# SAS_rev04.net
KiCad netlist of a schematic drawn in EAGLE
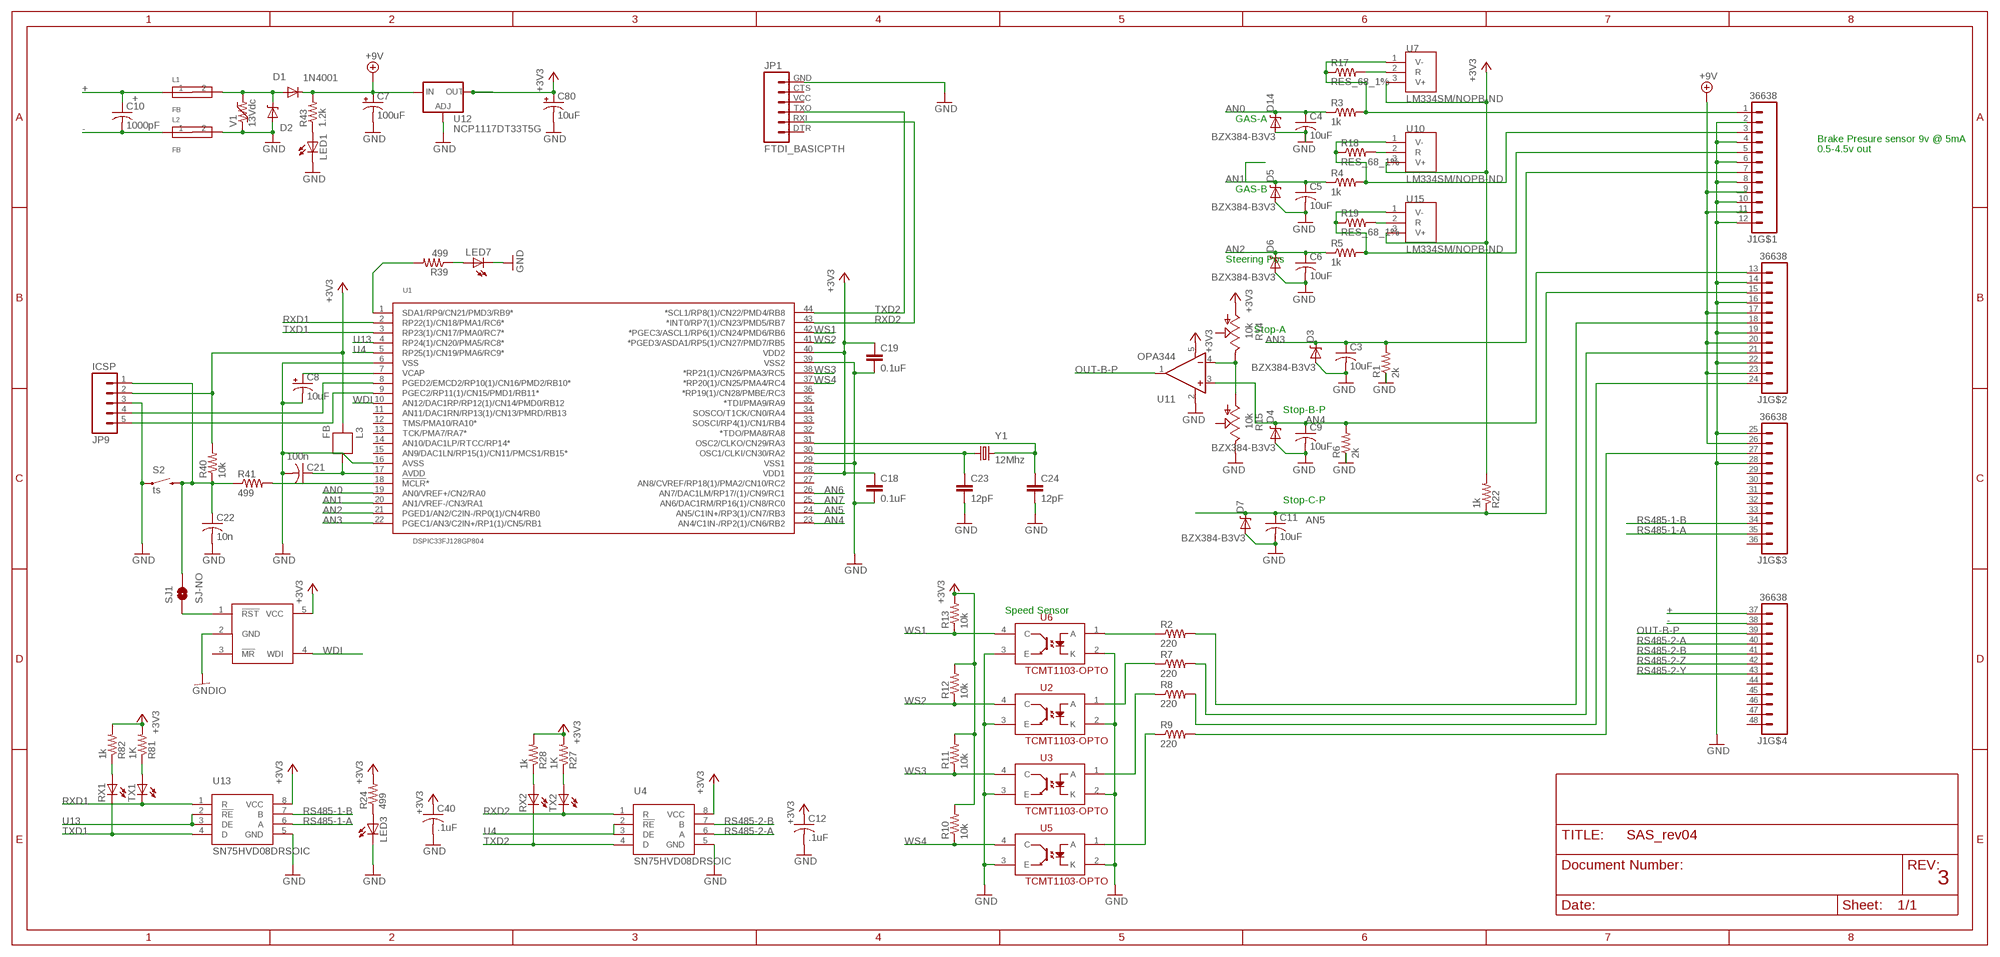
[diagram p0: schematic, sheet 1]

(export (version "E")
  (design (tool "Eeschema 10.0.6"))
  (components
    (comp (ref "C3")
      (value "10uF")
      (footprint "eagle-import:C0805")
      (libsource (lib "eagle-import") (part "C-USC0805"))
    )
    (comp (ref "C4")
      (value "10uF")
      (footprint "eagle-import:C0805")
      (libsource (lib "eagle-import") (part "C-USC0805"))
    )
    (comp (ref "C5")
      (value "10uF")
      (footprint "eagle-import:C0805")
      (libsource (lib "eagle-import") (part "C-USC0805"))
    )
    (comp (ref "C6")
      (value "10uF")
      (footprint "eagle-import:C0805")
      (libsource (lib "eagle-import") (part "C-USC0805"))
    )
    (comp (ref "C7")
      (value "100uF")
      (footprint "eagle-import:EIA7343")
      (libsource (lib "eagle-import") (part "CAP_POL7343"))
    )
    (comp (ref "C8")
      (value "10uF")
      (footprint "eagle-import:EIA3216-16V")
      (fields (field (name "PARTNO") "T491A106M016AT"))
      (libsource (lib "eagle-import") (part "CAP-POL_10UF_16V"))
    )
    (comp (ref "C9")
      (value "10uF")
      (footprint "eagle-import:C0805")
      (libsource (lib "eagle-import") (part "C-USC0805"))
    )
    (comp (ref "C10")
      (value "1000pF")
      (footprint "eagle-import:C1825")
      (libsource (lib "eagle-import") (part "C-USC1825"))
    )
    (comp (ref "C11")
      (value "10uF")
      (footprint "eagle-import:C0805")
      (libsource (lib "eagle-import") (part "C-USC0805"))
    )
    (comp (ref "C12")
      (value ".1uF")
      (footprint "eagle-import:0603")
      (fields (field (name "PARTNO") "CC0603ZRY5V9BB104"))
      (libsource (lib "eagle-import") (part "CAP_0.1UF_50V"))
    )
    (comp (ref "C18")
      (value "0.1uF")
      (footprint "eagle-import:0805")
      (libsource (lib "eagle-import") (part "CAP0805"))
    )
    (comp (ref "C19")
      (value "0.1uF")
      (footprint "eagle-import:0805")
      (libsource (lib "eagle-import") (part "CAP0805"))
    )
    (comp (ref "C21")
      (value "100n")
      (footprint "eagle-import:C0805")
      (libsource (lib "eagle-import") (part "C-USC0805"))
    )
    (comp (ref "C22")
      (value "10n")
      (footprint "eagle-import:0603")
      (fields (field (name "PARTNO") "CL10F103ZB8NNNC"))
      (libsource (lib "eagle-import") (part "CAP_10NF_50V"))
    )
    (comp (ref "C23")
      (value "12pF")
      (footprint "eagle-import:0805")
      (libsource (lib "eagle-import") (part "CAP0805"))
    )
    (comp (ref "C24")
      (value "12pF")
      (footprint "eagle-import:0805")
      (libsource (lib "eagle-import") (part "CAP0805"))
    )
    (comp (ref "C40")
      (value ".1uF")
      (footprint "eagle-import:0603")
      (fields (field (name "PARTNO") "CC0603ZRY5V9BB104"))
      (libsource (lib "eagle-import") (part "CAP_0.1UF_50V"))
    )
    (comp (ref "C80")
      (value "10uF")
      (footprint "eagle-import:POLC1206")
      (libsource (lib "eagle-import") (part "POLCAP"))
    )
    (comp (ref "D1")
      (value "1N4001")
      (footprint "eagle-import:SOD123")
      (libsource (lib "eagle-import") (part "DIODE-SOD123"))
    )
    (comp (ref "D2")
      (value "MM5Z30")
      (footprint "eagle-import:SOD-523F")
      (libsource (lib "eagle-import") (part "MM5Z30"))
    )
    (comp (ref "D3")
      (value "BZX384-B3V3")
      (footprint "eagle-import:SOD-323")
      (libsource (lib "eagle-import") (part "DIODE-ZENER-BZT52"))
    )
    (comp (ref "D4")
      (value "BZX384-B3V3")
      (footprint "eagle-import:SOD-323")
      (libsource (lib "eagle-import") (part "DIODE-ZENER-BZT52"))
    )
    (comp (ref "D5")
      (value "BZX384-B3V3")
      (footprint "eagle-import:SOD-323")
      (libsource (lib "eagle-import") (part "DIODE-ZENER-BZT52"))
    )
    (comp (ref "D6")
      (value "BZX384-B3V3")
      (footprint "eagle-import:SOD-323")
      (libsource (lib "eagle-import") (part "DIODE-ZENER-BZT52"))
    )
    (comp (ref "D7")
      (value "BZX384-B3V3")
      (footprint "eagle-import:SOD-323")
      (libsource (lib "eagle-import") (part "DIODE-ZENER-BZT52"))
    )
    (comp (ref "D14")
      (value "BZX384-B3V3")
      (footprint "eagle-import:SOD-323")
      (libsource (lib "eagle-import") (part "DIODE-ZENER-BZT52"))
    )
    (comp (ref "J1")
      (value "36638")
      (footprint "eagle-import:36638")
      (fields (field (name "PARTNO") "0366380002"))
      (libsource (lib "eagle-import") (part "36638"))
    )
    (comp (ref "JP1")
      (value "FTDI_BASICPTH")
      (footprint "eagle-import:FTDI_BASIC")
      (libsource (lib "eagle-import") (part "FTDI_BASICPTH"))
    )
    (comp (ref "JP9")
      (value "ICSP")
      (footprint "eagle-import:1X05_LOCK_LONGPADS")
      (libsource (lib "eagle-import") (part "M05LOCK_LONGPADS"))
    )
    (comp (ref "L1")
      (value "FB")
      (footprint "eagle-import:0603")
      (libsource (lib "eagle-import") (part "FERITEBEAD"))
    )
    (comp (ref "L2")
      (value "FB")
      (footprint "eagle-import:0603")
      (libsource (lib "eagle-import") (part "FERITEBEAD"))
    )
    (comp (ref "L3")
      (value "FB")
      (footprint "eagle-import:0603")
      (libsource (lib "eagle-import") (part "FB"))
    )
    (comp (ref "LED1")
      (value "LEDCHIP-LED0805")
      (footprint "eagle-import:CHIP-LED0805")
      (libsource (lib "eagle-import") (part "LEDCHIP-LED0805"))
    )
    (comp (ref "LED3")
      (value "LEDCHIP-LED0805")
      (footprint "eagle-import:CHIP-LED0805")
      (libsource (lib "eagle-import") (part "LEDCHIP-LED0805"))
    )
    (comp (ref "LED7")
      (value "LEDCHIP-LED0805")
      (footprint "eagle-import:CHIP-LED0805")
      (libsource (lib "eagle-import") (part "LEDCHIP-LED0805"))
    )
    (comp (ref "R1")
      (value "2k")
      (footprint "eagle-import:0805")
      (fields (field (name "PARTNO") "RC0805FR-072KL"))
      (libsource (lib "eagle-import") (part "FSAE Eletric_RES_2K_1%_0805"))
    )
    (comp (ref "R2")
      (value "220")
      (footprint "eagle-import:0603")
      (fields (field (name "PARTNO") "RC0603FR-07220RL"))
      (libsource (lib "eagle-import") (part "RES_220_1%"))
    )
    (comp (ref "R3")
      (value "1k")
      (footprint "eagle-import:0603")
      (fields (field (name "PARTNO") "RC0603JR-071KL"))
      (libsource (lib "eagle-import") (part "RES_1K_5%"))
    )
    (comp (ref "R4")
      (value "1k")
      (footprint "eagle-import:0603")
      (fields (field (name "PARTNO") "RC0603JR-071KL"))
      (libsource (lib "eagle-import") (part "RES_1K_5%"))
    )
    (comp (ref "R5")
      (value "1k")
      (footprint "eagle-import:0603")
      (fields (field (name "PARTNO") "RC0603JR-071KL"))
      (libsource (lib "eagle-import") (part "RES_1K_5%"))
    )
    (comp (ref "R6")
      (value "2k")
      (footprint "eagle-import:0805")
      (fields (field (name "PARTNO") "RC0805FR-072KL"))
      (libsource (lib "eagle-import") (part "FSAE Eletric_RES_2K_1%_0805"))
    )
    (comp (ref "R7")
      (value "220")
      (footprint "eagle-import:0603")
      (fields (field (name "PARTNO") "RC0603FR-07220RL"))
      (libsource (lib "eagle-import") (part "RES_220_1%"))
    )
    (comp (ref "R8")
      (value "220")
      (footprint "eagle-import:0603")
      (fields (field (name "PARTNO") "RC0603FR-07220RL"))
      (libsource (lib "eagle-import") (part "RES_220_1%"))
    )
    (comp (ref "R9")
      (value "220")
      (footprint "eagle-import:0603")
      (fields (field (name "PARTNO") "RC0603FR-07220RL"))
      (libsource (lib "eagle-import") (part "RES_220_1%"))
    )
    (comp (ref "R10")
      (value "10k")
      (footprint "eagle-import:0603")
      (fields (field (name "PARTNO") "RC0603FR-0710KL"))
      (libsource (lib "eagle-import") (part "RES_10K_1%"))
    )
    (comp (ref "R11")
      (value "10k")
      (footprint "eagle-import:0603")
      (fields (field (name "PARTNO") "RC0603FR-0710KL"))
      (libsource (lib "eagle-import") (part "RES_10K_1%"))
    )
    (comp (ref "R12")
      (value "10k")
      (footprint "eagle-import:0603")
      (fields (field (name "PARTNO") "RC0603FR-0710KL"))
      (libsource (lib "eagle-import") (part "RES_10K_1%"))
    )
    (comp (ref "R13")
      (value "10k")
      (footprint "eagle-import:0603")
      (fields (field (name "PARTNO") "RC0603FR-0710KL"))
      (libsource (lib "eagle-import") (part "RES_10K_1%"))
    )
    (comp (ref "R14")
      (value "10k")
      (footprint "eagle-import:PVG3")
      (fields (field (name "PARTNO") "PVG3A103C01R00"))
      (libsource (lib "eagle-import") (part "POT_10K_POT"))
    )
    (comp (ref "R15")
      (value "10k")
      (footprint "eagle-import:PVG3")
      (fields (field (name "PARTNO") "PVG3A103C01R00"))
      (libsource (lib "eagle-import") (part "POT_10K_POT"))
    )
    (comp (ref "R17")
      (value "RES_68_1%")
      (footprint "eagle-import:0603")
      (fields (field (name "PARTNO") "CRCW060368R0FKEA"))
      (libsource (lib "eagle-import") (part "RES_68_1%"))
    )
    (comp (ref "R18")
      (value "RES_68_1%")
      (footprint "eagle-import:0603")
      (fields (field (name "PARTNO") "CRCW060368R0FKEA"))
      (libsource (lib "eagle-import") (part "RES_68_1%"))
    )
    (comp (ref "R19")
      (value "RES_68_1%")
      (footprint "eagle-import:0603")
      (fields (field (name "PARTNO") "CRCW060368R0FKEA"))
      (libsource (lib "eagle-import") (part "RES_68_1%"))
    )
    (comp (ref "R22")
      (value "1k")
      (footprint "eagle-import:0805")
      (fields (field (name "PARTNO") "RC0805FR-071KL"))
      (libsource (lib "eagle-import") (part "FSAE Eletric_RES_1K_1%_0805"))
    )
    (comp (ref "R24")
      (value "499")
      (footprint "eagle-import:0603")
      (fields (field (name "PARTNO") "RC0603FR-07499RL"))
      (libsource (lib "eagle-import") (part "RES_499_1%"))
    )
    (comp (ref "R27")
      (value "1K")
      (footprint "eagle-import:0805")
      (fields (field (name "PARTNO") "RC0805FR-071KL"))
      (libsource (lib "eagle-import") (part "FSAE Eletric_RES_1K_1%_0805"))
    )
    (comp (ref "R28")
      (value "1k")
      (footprint "eagle-import:0805")
      (fields (field (name "PARTNO") "RC0805FR-071KL"))
      (libsource (lib "eagle-import") (part "FSAE Eletric_RES_1K_1%_0805"))
    )
    (comp (ref "R39")
      (value "499")
      (footprint "eagle-import:0603")
      (fields (field (name "PARTNO") "RC0603FR-07499RL"))
      (libsource (lib "eagle-import") (part "RES_499_1%"))
    )
    (comp (ref "R40")
      (value "10k")
      (footprint "eagle-import:0805")
      (fields (field (name "PARTNO") "RC0805FR-0710KL"))
      (libsource (lib "eagle-import") (part "FSAE Eletric_RES_10K_1%_0805"))
    )
    (comp (ref "R41")
      (value "499")
      (footprint "eagle-import:0805")
      (fields (field (name "PARTNO") "RC0805FR-07499RL"))
      (libsource (lib "eagle-import") (part "FSAE Eletric_RES_499_1%_0805"))
    )
    (comp (ref "R43")
      (value "1.2k")
      (footprint "eagle-import:0805")
      (fields (field (name "PARTNO") "RC0805FR-071K2L"))
      (libsource (lib "eagle-import") (part "RES_1.2K_1%_0805"))
    )
    (comp (ref "R81")
      (value "1K")
      (footprint "eagle-import:0603")
      (fields (field (name "PARTNO") "RC0603JR-071KL"))
      (libsource (lib "eagle-import") (part "RES_1K_5%"))
    )
    (comp (ref "R82")
      (value "1k")
      (footprint "eagle-import:0603")
      (fields (field (name "PARTNO") "RC0603JR-071KL"))
      (libsource (lib "eagle-import") (part "RES_1K_5%"))
    )
    (comp (ref "RX1")
      (value "LEDCHIPLED_0805")
      (footprint "eagle-import:CHIPLED_0805")
      (libsource (lib "eagle-import") (part "LEDCHIPLED_0805"))
    )
    (comp (ref "RX2")
      (value "LEDCHIPLED_0805")
      (footprint "eagle-import:CHIPLED_0805")
      (libsource (lib "eagle-import") (part "LEDCHIPLED_0805"))
    )
    (comp (ref "S2")
      (value "ts")
      (footprint "eagle-import:TACTILE-PTH")
      (libsource (lib "eagle-import") (part "SWITCH-MOMENTARY-2PTH"))
    )
    (comp (ref "SJ1")
      (value "SJ-NO")
      (footprint "eagle-import:SJ_2S-NO")
      (libsource (lib "eagle-import") (part "SOLDERJUMPERNO"))
    )
    (comp (ref "TX1")
      (value "LEDCHIPLED_0805")
      (footprint "eagle-import:CHIPLED_0805")
      (libsource (lib "eagle-import") (part "LEDCHIPLED_0805"))
    )
    (comp (ref "TX2")
      (value "LEDCHIPLED_0805")
      (footprint "eagle-import:CHIPLED_0805")
      (libsource (lib "eagle-import") (part "LEDCHIPLED_0805"))
    )
    (comp (ref "U1")
      (value "DSPIC33FJ128GP804")
      (footprint "eagle-import:TQFP-44")
      (fields (field (name "PARTNO") "DSPIC33FJ128GP804-I/PT"))
      (libsource (lib "eagle-import") (part "DSPIC33FJ128GP804"))
    )
    (comp (ref "U2")
      (value "TCMT1103-OPTO")
      (footprint "eagle-import:SSOP-4")
      (libsource (lib "eagle-import") (part "TCMT1103-OPTO"))
    )
    (comp (ref "U3")
      (value "TCMT1103-OPTO")
      (footprint "eagle-import:SSOP-4")
      (libsource (lib "eagle-import") (part "TCMT1103-OPTO"))
    )
    (comp (ref "U4")
      (value "SN75HVD08DRSOIC")
      (footprint "eagle-import:SO-8")
      (fields (field (name "PARTNO") "SN75176BDR"))
      (libsource (lib "eagle-import") (part "SN75HVD08DRSOIC"))
    )
    (comp (ref "U5")
      (value "TCMT1103-OPTO")
      (footprint "eagle-import:SSOP-4")
      (libsource (lib "eagle-import") (part "TCMT1103-OPTO"))
    )
    (comp (ref "U6")
      (value "TCMT1103-OPTO")
      (footprint "eagle-import:SSOP-4")
      (libsource (lib "eagle-import") (part "TCMT1103-OPTO"))
    )
    (comp (ref "U7")
      (value "LM334SM/NOPB-ND")
      (footprint "eagle-import:SO-8")
      (libsource (lib "eagle-import") (part "LM334SM/NOPB-ND"))
    )
    (comp (ref "U9")
      (value "MAX823")
      (footprint "eagle-import:SOT23-5L")
      (libsource (lib "eagle-import") (part "MAX823"))
    )
    (comp (ref "U10")
      (value "LM334SM/NOPB-ND")
      (footprint "eagle-import:SO-8")
      (libsource (lib "eagle-import") (part "LM334SM/NOPB-ND"))
    )
    (comp (ref "U11")
      (value "OPA344")
      (footprint "eagle-import:SOT23-5")
      (libsource (lib "eagle-import") (part "OPA344"))
    )
    (comp (ref "U12")
      (value "NCP1117DT33T5G")
      (footprint "eagle-import:V-REG_DPACK")
      (libsource (lib "eagle-import") (part "V_REG_317DPACK"))
    )
    (comp (ref "U13")
      (value "SN75HVD08DRSOIC")
      (footprint "eagle-import:SO-8")
      (fields (field (name "PARTNO") "SN75176BDR"))
      (libsource (lib "eagle-import") (part "SN75HVD08DRSOIC"))
    )
    (comp (ref "U15")
      (value "LM334SM/NOPB-ND")
      (footprint "eagle-import:SO-8")
      (libsource (lib "eagle-import") (part "LM334SM/NOPB-ND"))
    )
    (comp (ref "V1")
      (value "13Vdc")
      (footprint "eagle-import:0603")
      (libsource (lib "eagle-import") (part "VAR-RES"))
    )
    (comp (ref "Y1")
      (value "12Mhz")
      (footprint "eagle-import:CRYSTAL-SMD-5X3")
      (libsource (lib "eagle-import") (part "CRYSTAL5X3"))
    )
  )
  (nets
    (net (code "1") (name "+3V3") (class "Default")
      (node (ref "C12") (pin "1") (pinfunction "+_1") (pintype "passive"))
      (node (ref "C18") (pin "1") (pinfunction "1_1") (pintype "passive"))
      (node (ref "C19") (pin "1") (pinfunction "1_1") (pintype "passive"))
      (node (ref "C40") (pin "1") (pinfunction "+_1") (pintype "passive"))
      (node (ref "C80") (pin "1") (pinfunction "+_1") (pintype "passive"))
      (node (ref "JP9") (pin "2") (pinfunction "2_2") (pintype "passive"))
      (node (ref "L3") (pin "2") (pinfunction "P$2_2") (pintype "bidirectional"))
      (node (ref "R10") (pin "2") (pinfunction "2_2") (pintype "passive"))
      (node (ref "R11") (pin "2") (pinfunction "2_2") (pintype "passive"))
      (node (ref "R12") (pin "2") (pinfunction "2_2") (pintype "passive"))
      (node (ref "R13") (pin "2") (pinfunction "2_2") (pintype "passive"))
      (node (ref "R14") (pin "1") (pinfunction "CW_1") (pintype "passive"))
      (node (ref "R22") (pin "2") (pinfunction "2_2") (pintype "passive"))
      (node (ref "R24") (pin "2") (pinfunction "2_2") (pintype "passive"))
      (node (ref "R27") (pin "2") (pinfunction "2_2") (pintype "passive"))
      (node (ref "R28") (pin "2") (pinfunction "2_2") (pintype "passive"))
      (node (ref "R40") (pin "2") (pinfunction "2_2") (pintype "passive"))
      (node (ref "R81") (pin "2") (pinfunction "2_2") (pintype "passive"))
      (node (ref "R82") (pin "2") (pinfunction "2_2") (pintype "passive"))
      (node (ref "U1") (pin "28") (pinfunction "VDD1_28") (pintype "bidirectional"))
      (node (ref "U1") (pin "40") (pinfunction "VDD2_40") (pintype "bidirectional"))
      (node (ref "U10") (pin "3") (pinfunction "V+_3") (pintype "bidirectional"))
      (node (ref "U11") (pin "5") (pinfunction "V+_5") (pintype "power_in"))
      (node (ref "U12") (pin "4") (pinfunction "OUT_4") (pintype "output"))
      (node (ref "U13") (pin "8") (pinfunction "VCC_8") (pintype "bidirectional"))
      (node (ref "U15") (pin "3") (pinfunction "V+_3") (pintype "bidirectional"))
      (node (ref "U4") (pin "8") (pinfunction "VCC_8") (pintype "bidirectional"))
      (node (ref "U7") (pin "3") (pinfunction "V+_3") (pintype "bidirectional"))
      (node (ref "U9") (pin "5") (pinfunction "VCC_5") (pintype "bidirectional"))
    )
    (net (code "2") (name "+9V") (class "Default")
      (node (ref "C7") (pin "A") (pinfunction "+_A") (pintype "passive"))
      (node (ref "D1") (pin "C") (pinfunction "C_C") (pintype "passive"))
      (node (ref "J1") (pin "11") (pinfunction "11_11") (pintype "passive"))
      (node (ref "J1") (pin "17") (pinfunction "5_17") (pintype "passive"))
      (node (ref "J1") (pin "20") (pinfunction "8_20") (pintype "passive"))
      (node (ref "J1") (pin "23") (pinfunction "11_23") (pintype "passive"))
      (node (ref "J1") (pin "26") (pinfunction "2_26") (pintype "passive"))
      (node (ref "J1") (pin "9") (pinfunction "9_9") (pintype "passive"))
      (node (ref "R43") (pin "2") (pinfunction "2_2") (pintype "passive"))
      (node (ref "U12") (pin "3") (pinfunction "IN_3") (pintype "input"))
    )
    (net (code "3") (name "/+") (class "Default")
      (node (ref "C10") (pin "1") (pinfunction "1_1") (pintype "passive"))
      (node (ref "J1") (pin "37") (pinfunction "1_37") (pintype "passive"))
      (node (ref "L1") (pin "1") (pinfunction "P$1_1") (pintype "bidirectional"))
    )
    (net (code "4") (name "/-") (class "Default")
      (node (ref "C10") (pin "2") (pinfunction "2_2") (pintype "passive"))
      (node (ref "J1") (pin "38") (pinfunction "2_38") (pintype "passive"))
      (node (ref "L2") (pin "1") (pinfunction "P$1_1") (pintype "bidirectional"))
    )
    (net (code "5") (name "/AN0") (class "Default")
      (node (ref "C4") (pin "1") (pinfunction "1_1") (pintype "passive"))
      (node (ref "D14") (pin "1") (pinfunction "C_1") (pintype "passive"))
      (node (ref "R3") (pin "1") (pinfunction "1_1") (pintype "passive"))
      (node (ref "U1") (pin "19") (pinfunction "AN0/VREF+/CN2/RA0_19") (pintype "bidirectional"))
    )
    (net (code "6") (name "/AN1") (class "Default")
      (node (ref "C5") (pin "1") (pinfunction "1_1") (pintype "passive"))
      (node (ref "D5") (pin "1") (pinfunction "C_1") (pintype "passive"))
      (node (ref "R4") (pin "1") (pinfunction "1_1") (pintype "passive"))
      (node (ref "U1") (pin "20") (pinfunction "AN1/VREF-/CN3/RA1_20") (pintype "bidirectional"))
    )
    (net (code "7") (name "/AN2") (class "Default")
      (node (ref "C6") (pin "1") (pinfunction "1_1") (pintype "passive"))
      (node (ref "D6") (pin "1") (pinfunction "C_1") (pintype "passive"))
      (node (ref "R5") (pin "1") (pinfunction "1_1") (pintype "passive"))
      (node (ref "U1") (pin "21") (pinfunction "PGED1/AN2/C2IN-/RP0(1)/CN4/RB0_21") (pintype "bidirectional"))
    )
    (net (code "8") (name "/AN3") (class "Default")
      (node (ref "C3") (pin "1") (pinfunction "1_1") (pintype "passive"))
      (node (ref "D3") (pin "1") (pinfunction "C_1") (pintype "passive"))
      (node (ref "J1") (pin "7") (pinfunction "7_7") (pintype "passive"))
      (node (ref "R1") (pin "2") (pinfunction "2_2") (pintype "passive"))
      (node (ref "U1") (pin "22") (pinfunction "PGEC1/AN3/C2IN+/RP1(1)/CN5/RB1_22") (pintype "bidirectional"))
    )
    (net (code "9") (name "/AN4") (class "Default")
      (node (ref "C9") (pin "1") (pinfunction "1_1") (pintype "passive"))
      (node (ref "D4") (pin "1") (pinfunction "C_1") (pintype "passive"))
      (node (ref "J1") (pin "13") (pinfunction "1_13") (pintype "passive"))
      (node (ref "R6") (pin "2") (pinfunction "2_2") (pintype "passive"))
      (node (ref "U1") (pin "23") (pinfunction "AN4/C1IN-/RP2(1)/CN6/RB2_23") (pintype "bidirectional"))
      (node (ref "U11") (pin "3") (pinfunction "+IN_3") (pintype "input"))
    )
    (net (code "10") (name "/AN5") (class "Default")
      (node (ref "C11") (pin "1") (pinfunction "1_1") (pintype "passive"))
      (node (ref "D7") (pin "1") (pinfunction "C_1") (pintype "passive"))
      (node (ref "J1") (pin "15") (pinfunction "3_15") (pintype "passive"))
      (node (ref "R22") (pin "1") (pinfunction "1_1") (pintype "passive"))
      (node (ref "U1") (pin "24") (pinfunction "AN5/C1IN+/RP3(1)/CN7/RB3_24") (pintype "bidirectional"))
    )
    (net (code "11") (name "/AN6") (class "Default")
      (node (ref "U1") (pin "26") (pinfunction "AN7/DAC1LM/RP17/(1)/CN9/RC1_26") (pintype "bidirectional"))
    )
    (net (code "12") (name "/AN7") (class "Default")
      (node (ref "U1") (pin "25") (pinfunction "AN6/DAC1RM/RP16(1)/CN8/RC0_25") (pintype "bidirectional"))
    )
    (net (code "13") (name "/OUT-B-P") (class "Default")
      (node (ref "J1") (pin "39") (pinfunction "3_39") (pintype "passive"))
      (node (ref "U11") (pin "1") (pinfunction "OUT_1") (pintype "output"))
    )
    (net (code "14") (name "/RS485-1-A") (class "Default")
      (node (ref "J1") (pin "35") (pinfunction "11_35") (pintype "passive"))
      (node (ref "U13") (pin "6") (pinfunction "A_6") (pintype "bidirectional"))
    )
    (net (code "15") (name "/RS485-1-B") (class "Default")
      (node (ref "J1") (pin "34") (pinfunction "10_34") (pintype "passive"))
      (node (ref "U13") (pin "7") (pinfunction "B_7") (pintype "bidirectional"))
    )
    (net (code "16") (name "/RS485-2-A") (class "Default")
      (node (ref "J1") (pin "40") (pinfunction "4_40") (pintype "passive"))
      (node (ref "U4") (pin "6") (pinfunction "A_6") (pintype "bidirectional"))
    )
    (net (code "17") (name "/RS485-2-B") (class "Default")
      (node (ref "J1") (pin "41") (pinfunction "5_41") (pintype "passive"))
      (node (ref "U4") (pin "7") (pinfunction "B_7") (pintype "bidirectional"))
    )
    (net (code "18") (name "/RS485-2-Y") (class "Default")
      (node (ref "J1") (pin "43") (pinfunction "7_43") (pintype "passive"))
    )
    (net (code "19") (name "/RS485-2-Z") (class "Default")
      (node (ref "J1") (pin "42") (pinfunction "6_42") (pintype "passive"))
    )
    (net (code "20") (name "/RXD1") (class "Default")
      (node (ref "TX1") (pin "C") (pinfunction "C_C") (pintype "passive"))
      (node (ref "U1") (pin "2") (pinfunction "RP22(1)/CN18/PMA1/RC6*_2") (pintype "bidirectional"))
      (node (ref "U13") (pin "1") (pinfunction "R_1") (pintype "bidirectional"))
    )
    (net (code "21") (name "/RXD2") (class "Default")
      (node (ref "JP1") (pin "RXI") (pinfunction "2_RXI") (pintype "passive"))
      (node (ref "TX2") (pin "C") (pinfunction "C_C") (pintype "passive"))
      (node (ref "U1") (pin "43") (pinfunction "*INT0/RP7(1)/CN23/PMD5/RB7_43") (pintype "bidirectional"))
      (node (ref "U4") (pin "1") (pinfunction "R_1") (pintype "bidirectional"))
    )
    (net (code "22") (name "/TXD1") (class "Default")
      (node (ref "RX1") (pin "C") (pinfunction "C_C") (pintype "passive"))
      (node (ref "U1") (pin "3") (pinfunction "RP23(1)/CN17/PMA0/RC7*_3") (pintype "bidirectional"))
      (node (ref "U13") (pin "4") (pinfunction "D_4") (pintype "bidirectional"))
    )
    (net (code "23") (name "/TXD2") (class "Default")
      (node (ref "JP1") (pin "TXO") (pinfunction "3_TXO") (pintype "passive"))
      (node (ref "RX2") (pin "C") (pinfunction "C_C") (pintype "passive"))
      (node (ref "U1") (pin "44") (pinfunction "*SCL1/RP8(1)/CN22/PMD4/RB8_44") (pintype "bidirectional"))
      (node (ref "U4") (pin "4") (pinfunction "D_4") (pintype "bidirectional"))
    )
    (net (code "24") (name "/U4") (class "Default")
      (node (ref "U1") (pin "5") (pinfunction "RP25(1)/CN19/PMA6/RC9*_5") (pintype "bidirectional"))
      (node (ref "U4") (pin "2") (pinfunction "~{RE}_2") (pintype "bidirectional"))
      (node (ref "U4") (pin "3") (pinfunction "DE_3") (pintype "bidirectional"))
    )
    (net (code "25") (name "/U13") (class "Default")
      (node (ref "U1") (pin "4") (pinfunction "RP24(1)/CN20/PMA5/RC8*_4") (pintype "bidirectional"))
      (node (ref "U13") (pin "2") (pinfunction "~{RE}_2") (pintype "bidirectional"))
      (node (ref "U13") (pin "3") (pinfunction "DE_3") (pintype "bidirectional"))
    )
    (net (code "26") (name "/WDI") (class "Default")
      (node (ref "U1") (pin "10") (pinfunction "AN12/DAC1RP/RP12(1)/CN14/PMD0/RB12_10") (pintype "bidirectional"))
      (node (ref "U9") (pin "4") (pinfunction "WDI_4") (pintype "bidirectional"))
    )
    (net (code "27") (name "/WS1") (class "Default")
      (node (ref "R13") (pin "1") (pinfunction "1_1") (pintype "passive"))
      (node (ref "U1") (pin "42") (pinfunction "*PGEC3/ASCL1/RP6(1)/CN24/PMD6/RB6_42") (pintype "bidirectional"))
      (node (ref "U6") (pin "4") (pinfunction "C_4") (pintype "bidirectional"))
    )
    (net (code "28") (name "/WS2") (class "Default")
      (node (ref "R12") (pin "1") (pinfunction "1_1") (pintype "passive"))
      (node (ref "U1") (pin "41") (pinfunction "*PGED3/ASDA1/RP5(1)/CN27/PMD7/RB5_41") (pintype "bidirectional"))
      (node (ref "U2") (pin "4") (pinfunction "C_4") (pintype "bidirectional"))
    )
    (net (code "29") (name "/WS3") (class "Default")
      (node (ref "R11") (pin "1") (pinfunction "1_1") (pintype "passive"))
      (node (ref "U1") (pin "38") (pinfunction "*RP21(1)/CN26/PMA3/RC5_38") (pintype "bidirectional"))
      (node (ref "U3") (pin "4") (pinfunction "C_4") (pintype "bidirectional"))
    )
    (net (code "30") (name "/WS4") (class "Default")
      (node (ref "R10") (pin "1") (pinfunction "1_1") (pintype "passive"))
      (node (ref "U1") (pin "37") (pinfunction "*RP20(1)/CN25/PMA4/RC4_37") (pintype "bidirectional"))
      (node (ref "U5") (pin "4") (pinfunction "C_4") (pintype "bidirectional"))
    )
    (net (code "31") (name "GND") (class "Default")
      (node (ref "C11") (pin "2") (pinfunction "2_2") (pintype "passive"))
      (node (ref "C12") (pin "2") (pinfunction "-_2") (pintype "passive"))
      (node (ref "C18") (pin "2") (pinfunction "2_2") (pintype "passive"))
      (node (ref "C19") (pin "2") (pinfunction "2_2") (pintype "passive"))
      (node (ref "C21") (pin "2") (pinfunction "2_2") (pintype "passive"))
      (node (ref "C22") (pin "2") (pinfunction "-_2") (pintype "passive"))
      (node (ref "C23") (pin "2") (pinfunction "2_2") (pintype "passive"))
      (node (ref "C24") (pin "2") (pinfunction "2_2") (pintype "passive"))
      (node (ref "C3") (pin "2") (pinfunction "2_2") (pintype "passive"))
      (node (ref "C4") (pin "2") (pinfunction "2_2") (pintype "passive"))
      (node (ref "C40") (pin "2") (pinfunction "-_2") (pintype "passive"))
      (node (ref "C5") (pin "2") (pinfunction "2_2") (pintype "passive"))
      (node (ref "C6") (pin "2") (pinfunction "2_2") (pintype "passive"))
      (node (ref "C7") (pin "C") (pinfunction "-_C") (pintype "passive"))
      (node (ref "C8") (pin "C") (pinfunction "-_C") (pintype "passive"))
      (node (ref "C80") (pin "2") (pinfunction "-_2") (pintype "passive"))
      (node (ref "C9") (pin "2") (pinfunction "2_2") (pintype "passive"))
      (node (ref "D14") (pin "2") (pinfunction "A_2") (pintype "passive"))
      (node (ref "D2") (pin "A") (pinfunction "A_A") (pintype "passive"))
      (node (ref "D3") (pin "2") (pinfunction "A_2") (pintype "passive"))
      (node (ref "D4") (pin "2") (pinfunction "A_2") (pintype "passive"))
      (node (ref "D5") (pin "2") (pinfunction "A_2") (pintype "passive"))
      (node (ref "D6") (pin "2") (pinfunction "A_2") (pintype "passive"))
      (node (ref "D7") (pin "2") (pinfunction "A_2") (pintype "passive"))
      (node (ref "J1") (pin "10") (pinfunction "10_10") (pintype "passive"))
      (node (ref "J1") (pin "12") (pinfunction "12_12") (pintype "passive"))
      (node (ref "J1") (pin "14") (pinfunction "2_14") (pintype "passive"))
      (node (ref "J1") (pin "16") (pinfunction "4_16") (pintype "passive"))
      (node (ref "J1") (pin "19") (pinfunction "7_19") (pintype "passive"))
      (node (ref "J1") (pin "2") (pinfunction "2_2") (pintype "passive"))
      (node (ref "J1") (pin "22") (pinfunction "10_22") (pintype "passive"))
      (node (ref "J1") (pin "25") (pinfunction "1_25") (pintype "passive"))
      (node (ref "J1") (pin "28") (pinfunction "4_28") (pintype "passive"))
      (node (ref "J1") (pin "4") (pinfunction "4_4") (pintype "passive"))
      (node (ref "J1") (pin "6") (pinfunction "6_6") (pintype "passive"))
      (node (ref "J1") (pin "8") (pinfunction "8_8") (pintype "passive"))
      (node (ref "JP1") (pin "GND") (pinfunction "6_GND") (pintype "passive"))
      (node (ref "JP9") (pin "3") (pinfunction "3_3") (pintype "passive"))
      (node (ref "L2") (pin "2") (pinfunction "P$2_2") (pintype "bidirectional"))
      (node (ref "LED1") (pin "C") (pinfunction "C_C") (pintype "passive"))
      (node (ref "LED3") (pin "C") (pinfunction "C_C") (pintype "passive"))
      (node (ref "LED7") (pin "C") (pinfunction "C_C") (pintype "passive"))
      (node (ref "R1") (pin "1") (pinfunction "1_1") (pintype "passive"))
      (node (ref "R15") (pin "3") (pinfunction "CCW_3") (pintype "passive"))
      (node (ref "R6") (pin "1") (pinfunction "1_1") (pintype "passive"))
      (node (ref "S2") (pin "1") (pinfunction "1_1") (pintype "passive"))
      (node (ref "U1") (pin "16") (pinfunction "AVSS_16") (pintype "bidirectional"))
      (node (ref "U1") (pin "29") (pinfunction "VSS1_29") (pintype "bidirectional"))
      (node (ref "U1") (pin "39") (pinfunction "VSS2_39") (pintype "bidirectional"))
      (node (ref "U1") (pin "6") (pinfunction "VSS_6") (pintype "bidirectional"))
      (node (ref "U11") (pin "2") (pinfunction "V-_2") (pintype "power_in"))
      (node (ref "U12") (pin "1") (pinfunction "ADJ_1") (pintype "input"))
      (node (ref "U13") (pin "5") (pinfunction "GND_5") (pintype "bidirectional"))
      (node (ref "U2") (pin "2") (pinfunction "K_2") (pintype "bidirectional"))
      (node (ref "U2") (pin "3") (pinfunction "E_3") (pintype "bidirectional"))
      (node (ref "U3") (pin "2") (pinfunction "K_2") (pintype "bidirectional"))
      (node (ref "U3") (pin "3") (pinfunction "E_3") (pintype "bidirectional"))
      (node (ref "U4") (pin "5") (pinfunction "GND_5") (pintype "bidirectional"))
      (node (ref "U5") (pin "2") (pinfunction "K_2") (pintype "bidirectional"))
      (node (ref "U5") (pin "3") (pinfunction "E_3") (pintype "bidirectional"))
      (node (ref "U6") (pin "2") (pinfunction "K_2") (pintype "bidirectional"))
      (node (ref "U6") (pin "3") (pinfunction "E_3") (pintype "bidirectional"))
      (node (ref "V1") (pin "1") (pinfunction "1_1") (pintype "passive"))
    )
    (net (code "32") (name "GNDIO") (class "Default")
      (node (ref "U9") (pin "2") (pinfunction "GND_2") (pintype "bidirectional"))
    )
    (net (code "33") (name "Net-(C8-+)") (class "Default")
      (node (ref "C8") (pin "A") (pinfunction "+_A") (pintype "passive"))
      (node (ref "U1") (pin "7") (pinfunction "VCAP_7") (pintype "bidirectional"))
    )
    (net (code "34") (name "Net-(C22-+)") (class "Default")
      (node (ref "C22") (pin "1") (pinfunction "+_1") (pintype "passive"))
      (node (ref "JP9") (pin "1") (pinfunction "1_1") (pintype "passive"))
      (node (ref "R40") (pin "1") (pinfunction "1_1") (pintype "passive"))
      (node (ref "R41") (pin "1") (pinfunction "1_1") (pintype "passive"))
      (node (ref "S2") (pin "3") (pinfunction "2_3") (pintype "passive"))
      (node (ref "SJ1") (pin "2") (pinfunction "2_2") (pintype "passive"))
    )
    (net (code "35") (name "Net-(J1B-6)") (class "Default")
      (node (ref "J1") (pin "18") (pinfunction "6_18") (pintype "passive"))
      (node (ref "R2") (pin "2") (pinfunction "2_2") (pintype "passive"))
    )
    (net (code "36") (name "Net-(J1B-9)") (class "Default")
      (node (ref "J1") (pin "21") (pinfunction "9_21") (pintype "passive"))
      (node (ref "R7") (pin "2") (pinfunction "2_2") (pintype "passive"))
    )
    (net (code "37") (name "Net-(J1B-12)") (class "Default")
      (node (ref "J1") (pin "24") (pinfunction "12_24") (pintype "passive"))
      (node (ref "R8") (pin "2") (pinfunction "2_2") (pintype "passive"))
    )
    (net (code "38") (name "Net-(J1C-3)") (class "Default")
      (node (ref "J1") (pin "27") (pinfunction "3_27") (pintype "passive"))
      (node (ref "R9") (pin "2") (pinfunction "2_2") (pintype "passive"))
    )
    (net (code "39") (name "Net-(L1-P$2)") (class "Default")
      (node (ref "D1") (pin "A") (pinfunction "A_A") (pintype "passive"))
      (node (ref "D2") (pin "C") (pinfunction "C_C") (pintype "passive"))
      (node (ref "L1") (pin "2") (pinfunction "P$2_2") (pintype "bidirectional"))
      (node (ref "V1") (pin "2") (pinfunction "2_2") (pintype "passive"))
    )
    (net (code "40") (name "Net-(L3-P$1)") (class "Default")
      (node (ref "C21") (pin "1") (pinfunction "1_1") (pintype "passive"))
      (node (ref "L3") (pin "1") (pinfunction "P$1_1") (pintype "bidirectional"))
      (node (ref "U1") (pin "17") (pinfunction "AVDD_17") (pintype "bidirectional"))
    )
    (net (code "41") (name "Net-(LED1-PadA)") (class "Default")
      (node (ref "LED1") (pin "A") (pinfunction "A_A") (pintype "passive"))
      (node (ref "R43") (pin "1") (pinfunction "1_1") (pintype "passive"))
    )
    (net (code "42") (name "Net-(LED3-PadA)") (class "Default")
      (node (ref "LED3") (pin "A") (pinfunction "A_A") (pintype "passive"))
      (node (ref "R24") (pin "1") (pinfunction "1_1") (pintype "passive"))
    )
    (net (code "43") (name "Net-(LED7-PadA)") (class "Default")
      (node (ref "LED7") (pin "A") (pinfunction "A_A") (pintype "passive"))
      (node (ref "R39") (pin "1") (pinfunction "1_1") (pintype "passive"))
    )
    (net (code "44") (name "Net-(R14-CCW)") (class "Default")
      (node (ref "R14") (pin "3") (pinfunction "CCW_3") (pintype "passive"))
      (node (ref "R15") (pin "1") (pinfunction "CW_1") (pintype "passive"))
      (node (ref "U11") (pin "4") (pinfunction "-IN_4") (pintype "input"))
    )
    (net (code "45") (name "Net-(R27-Pad1)") (class "Default")
      (node (ref "R27") (pin "1") (pinfunction "1_1") (pintype "passive"))
      (node (ref "TX2") (pin "A") (pinfunction "A_A") (pintype "passive"))
    )
    (net (code "46") (name "Net-(R28-Pad1)") (class "Default")
      (node (ref "R28") (pin "1") (pinfunction "1_1") (pintype "passive"))
      (node (ref "RX2") (pin "A") (pinfunction "A_A") (pintype "passive"))
    )
    (net (code "47") (name "Net-(R81-Pad1)") (class "Default")
      (node (ref "R81") (pin "1") (pinfunction "1_1") (pintype "passive"))
      (node (ref "TX1") (pin "A") (pinfunction "A_A") (pintype "passive"))
    )
    (net (code "48") (name "Net-(R82-Pad1)") (class "Default")
      (node (ref "R82") (pin "1") (pinfunction "1_1") (pintype "passive"))
      (node (ref "RX1") (pin "A") (pinfunction "A_A") (pintype "passive"))
    )
    (net (code "49") (name "Net-(U1-OSC1{slash}CLKI{slash}CN30{slash}RA2)") (class "Default")
      (node (ref "C23") (pin "1") (pinfunction "1_1") (pintype "passive"))
      (node (ref "U1") (pin "30") (pinfunction "OSC1/CLKI/CN30/RA2_30") (pintype "bidirectional"))
      (node (ref "Y1") (pin "1") (pinfunction "1_1") (pintype "passive"))
    )
    (net (code "50") (name "Net-(U1-OSC2{slash}CLKO{slash}CN29{slash}RA3)") (class "Default")
      (node (ref "C24") (pin "1") (pinfunction "1_1") (pintype "passive"))
      (node (ref "U1") (pin "31") (pinfunction "OSC2/CLKO/CN29/RA3_31") (pintype "bidirectional"))
      (node (ref "Y1") (pin "3") (pinfunction "2_3") (pintype "passive"))
    )
    (net (code "51") (name "Net-(U1-PGEC2{slash}RP11(1){slash}CN15{slash}PMD1{slash}RB11*)") (class "Default")
      (node (ref "JP9") (pin "5") (pinfunction "5_5") (pintype "passive"))
      (node (ref "U1") (pin "9") (pinfunction "PGEC2/RP11(1)/CN15/PMD1/RB11*_9") (pintype "bidirectional"))
    )
    (net (code "52") (name "Net-(U1-PGED2{slash}EMCD2{slash}RP10(1){slash}CN16{slash}PMD2{slash}RB10*)") (class "Default")
      (node (ref "JP9") (pin "4") (pinfunction "4_4") (pintype "passive"))
      (node (ref "U1") (pin "8") (pinfunction "PGED2/EMCD2/RP10(1)/CN16/PMD2/RB10*_8") (pintype "bidirectional"))
    )
    (net (code "53") (name "Net-(U1-SDA1{slash}RP9{slash}CN21{slash}PMD3{slash}RB9*)") (class "Default")
      (node (ref "R39") (pin "2") (pinfunction "2_2") (pintype "passive"))
      (node (ref "U1") (pin "1") (pinfunction "SDA1/RP9/CN21/PMD3/RB9*_1") (pintype "bidirectional"))
    )
    (net (code "54") (name "Net-(U1-~{MCLR}*)") (class "Default")
      (node (ref "R41") (pin "2") (pinfunction "2_2") (pintype "passive"))
      (node (ref "U1") (pin "18") (pinfunction "~{MCLR}*_18") (pintype "bidirectional"))
    )
    (net (code "55") (name "Net-(U2-A)") (class "Default")
      (node (ref "R7") (pin "1") (pinfunction "1_1") (pintype "passive"))
      (node (ref "U2") (pin "1") (pinfunction "A_1") (pintype "bidirectional"))
    )
    (net (code "56") (name "Net-(U3-A)") (class "Default")
      (node (ref "R8") (pin "1") (pinfunction "1_1") (pintype "passive"))
      (node (ref "U3") (pin "1") (pinfunction "A_1") (pintype "bidirectional"))
    )
    (net (code "57") (name "Net-(U5-A)") (class "Default")
      (node (ref "R9") (pin "1") (pinfunction "1_1") (pintype "passive"))
      (node (ref "U5") (pin "1") (pinfunction "A_1") (pintype "bidirectional"))
    )
    (net (code "58") (name "Net-(U6-A)") (class "Default")
      (node (ref "R2") (pin "1") (pinfunction "1_1") (pintype "passive"))
      (node (ref "U6") (pin "1") (pinfunction "A_1") (pintype "bidirectional"))
    )
    (net (code "59") (name "Net-(U7-R)") (class "Default")
      (node (ref "R17") (pin "2") (pinfunction "2_2") (pintype "passive"))
      (node (ref "U7") (pin "2") (pinfunction "R_2") (pintype "bidirectional"))
    )
    (net (code "60") (name "Net-(U7-V-)") (class "Default")
      (node (ref "J1") (pin "1") (pinfunction "1_1") (pintype "passive"))
      (node (ref "R17") (pin "1") (pinfunction "1_1") (pintype "passive"))
      (node (ref "R3") (pin "2") (pinfunction "2_2") (pintype "passive"))
      (node (ref "U7") (pin "1") (pinfunction "V-_1") (pintype "bidirectional"))
    )
    (net (code "61") (name "Net-(U9-~{RST})") (class "Default")
      (node (ref "SJ1") (pin "1") (pinfunction "1_1") (pintype "passive"))
      (node (ref "U9") (pin "1") (pinfunction "~{RST}_1") (pintype "bidirectional"))
    )
    (net (code "62") (name "Net-(U10-R)") (class "Default")
      (node (ref "R18") (pin "2") (pinfunction "2_2") (pintype "passive"))
      (node (ref "U10") (pin "2") (pinfunction "R_2") (pintype "bidirectional"))
    )
    (net (code "63") (name "Net-(U10-V-)") (class "Default")
      (node (ref "J1") (pin "3") (pinfunction "3_3") (pintype "passive"))
      (node (ref "R18") (pin "1") (pinfunction "1_1") (pintype "passive"))
      (node (ref "R4") (pin "2") (pinfunction "2_2") (pintype "passive"))
      (node (ref "U10") (pin "1") (pinfunction "V-_1") (pintype "bidirectional"))
    )
    (net (code "64") (name "Net-(U15-R)") (class "Default")
      (node (ref "R19") (pin "2") (pinfunction "2_2") (pintype "passive"))
      (node (ref "U15") (pin "2") (pinfunction "R_2") (pintype "bidirectional"))
    )
    (net (code "65") (name "Net-(U15-V-)") (class "Default")
      (node (ref "J1") (pin "5") (pinfunction "5_5") (pintype "passive"))
      (node (ref "R19") (pin "1") (pinfunction "1_1") (pintype "passive"))
      (node (ref "R5") (pin "2") (pinfunction "2_2") (pintype "passive"))
      (node (ref "U15") (pin "1") (pinfunction "V-_1") (pintype "bidirectional"))
    )
    (net (code "66") (name "unconnected-(J1C-5-Pad29)") (class "Default")
      (node (ref "J1") (pin "29") (pinfunction "5_29") (pintype "passive"))
    )
    (net (code "67") (name "unconnected-(J1C-6-Pad30)") (class "Default")
      (node (ref "J1") (pin "30") (pinfunction "6_30") (pintype "passive"))
    )
    (net (code "68") (name "unconnected-(J1C-7-Pad31)") (class "Default")
      (node (ref "J1") (pin "31") (pinfunction "7_31") (pintype "passive"))
    )
    (net (code "69") (name "unconnected-(J1C-8-Pad32)") (class "Default")
      (node (ref "J1") (pin "32") (pinfunction "8_32") (pintype "passive"))
    )
    (net (code "70") (name "unconnected-(J1C-9-Pad33)") (class "Default")
      (node (ref "J1") (pin "33") (pinfunction "9_33") (pintype "passive"))
    )
    (net (code "71") (name "unconnected-(J1C-12-Pad36)") (class "Default")
      (node (ref "J1") (pin "36") (pinfunction "12_36") (pintype "passive"))
    )
    (net (code "72") (name "unconnected-(J1D-8-Pad44)") (class "Default")
      (node (ref "J1") (pin "44") (pinfunction "8_44") (pintype "passive"))
    )
    (net (code "73") (name "unconnected-(J1D-9-Pad45)") (class "Default")
      (node (ref "J1") (pin "45") (pinfunction "9_45") (pintype "passive"))
    )
    (net (code "74") (name "unconnected-(J1D-10-Pad46)") (class "Default")
      (node (ref "J1") (pin "46") (pinfunction "10_46") (pintype "passive"))
    )
    (net (code "75") (name "unconnected-(J1D-11-Pad47)") (class "Default")
      (node (ref "J1") (pin "47") (pinfunction "11_47") (pintype "passive"))
    )
    (net (code "76") (name "unconnected-(J1D-12-Pad48)") (class "Default")
      (node (ref "J1") (pin "48") (pinfunction "12_48") (pintype "passive"))
    )
    (net (code "77") (name "unconnected-(JP1-1-PadDTR)") (class "Default")
      (node (ref "JP1") (pin "DTR") (pinfunction "1_DTR") (pintype "passive"))
    )
    (net (code "78") (name "unconnected-(JP1-4-PadVCC)") (class "Default")
      (node (ref "JP1") (pin "VCC") (pinfunction "4_VCC") (pintype "passive"))
    )
    (net (code "79") (name "unconnected-(JP1-5-PadCTS)") (class "Default")
      (node (ref "JP1") (pin "CTS") (pinfunction "5_CTS") (pintype "passive"))
    )
    (net (code "80") (name "unconnected-(R14-W-Pad2)") (class "Default")
      (node (ref "R14") (pin "2") (pinfunction "W_2") (pintype "passive"))
    )
    (net (code "81") (name "unconnected-(R15-W-Pad2)") (class "Default")
      (node (ref "R15") (pin "2") (pinfunction "W_2") (pintype "passive"))
    )
    (net (code "82") (name "unconnected-(U1-*RP19(1){slash}CN28{slash}PMBE{slash}RC3-Pad36)") (class "Default")
      (node (ref "U1") (pin "36") (pinfunction "*RP19(1)/CN28/PMBE/RC3_36") (pintype "bidirectional"))
    )
    (net (code "83") (name "unconnected-(U1-*TDI{slash}PMA9{slash}RA9-Pad35)") (class "Default")
      (node (ref "U1") (pin "35") (pinfunction "*TDI/PMA9/RA9_35") (pintype "bidirectional"))
    )
    (net (code "84") (name "unconnected-(U1-*TDO{slash}PMA8{slash}RA8-Pad32)") (class "Default")
      (node (ref "U1") (pin "32") (pinfunction "*TDO/PMA8/RA8_32") (pintype "bidirectional"))
    )
    (net (code "85") (name "unconnected-(U1-AN8{slash}CVREF{slash}RP18(1){slash}PMA2{slash}CN10{slash}RC2-Pad27)") (class "Default")
      (node (ref "U1") (pin "27") (pinfunction "AN8/CVREF/RP18(1)/PMA2/CN10/RC2_27") (pintype "bidirectional"))
    )
    (net (code "86") (name "unconnected-(U1-AN9{slash}DAC1LN{slash}RP15(1){slash}CN11{slash}PMCS1{slash}RB15*-Pad15)") (class "Default")
      (node (ref "U1") (pin "15") (pinfunction "AN9/DAC1LN/RP15(1)/CN11/PMCS1/RB15*_15") (pintype "bidirectional"))
    )
    (net (code "87") (name "unconnected-(U1-AN10{slash}DAC1LP{slash}RTCC{slash}RP14*-Pad14)") (class "Default")
      (node (ref "U1") (pin "14") (pinfunction "AN10/DAC1LP/RTCC/RP14*_14") (pintype "bidirectional"))
    )
    (net (code "88") (name "unconnected-(U1-AN11{slash}DAC1RN{slash}RP13(1){slash}CN13{slash}PMRD{slash}RB13-Pad11)") (class "Default")
      (node (ref "U1") (pin "11") (pinfunction "AN11/DAC1RN/RP13(1)/CN13/PMRD/RB13_11") (pintype "bidirectional"))
    )
    (net (code "89") (name "unconnected-(U1-SOSCI{slash}RP4(1){slash}CN1{slash}RB4-Pad33)") (class "Default")
      (node (ref "U1") (pin "33") (pinfunction "SOSCI/RP4(1)/CN1/RB4_33") (pintype "bidirectional"))
    )
    (net (code "90") (name "unconnected-(U1-SOSCO{slash}T1CK{slash}CN0{slash}RA4-Pad34)") (class "Default")
      (node (ref "U1") (pin "34") (pinfunction "SOSCO/T1CK/CN0/RA4_34") (pintype "bidirectional"))
    )
    (net (code "91") (name "unconnected-(U1-TCK{slash}PMA7{slash}RA7*-Pad13)") (class "Default")
      (node (ref "U1") (pin "13") (pinfunction "TCK/PMA7/RA7*_13") (pintype "bidirectional"))
    )
    (net (code "92") (name "unconnected-(U1-TMS{slash}PMA10{slash}RA10*-Pad12)") (class "Default")
      (node (ref "U1") (pin "12") (pinfunction "TMS/PMA10/RA10*_12") (pintype "bidirectional"))
    )
    (net (code "93") (name "unconnected-(U9-~{MR}-Pad3)") (class "Default")
      (node (ref "U9") (pin "3") (pinfunction "~{MR}_3") (pintype "bidirectional"))
    )
  )
)
